# power_selectable_5v_3_3v.net
KiCad netlist of a schematic drawn in EAGLE
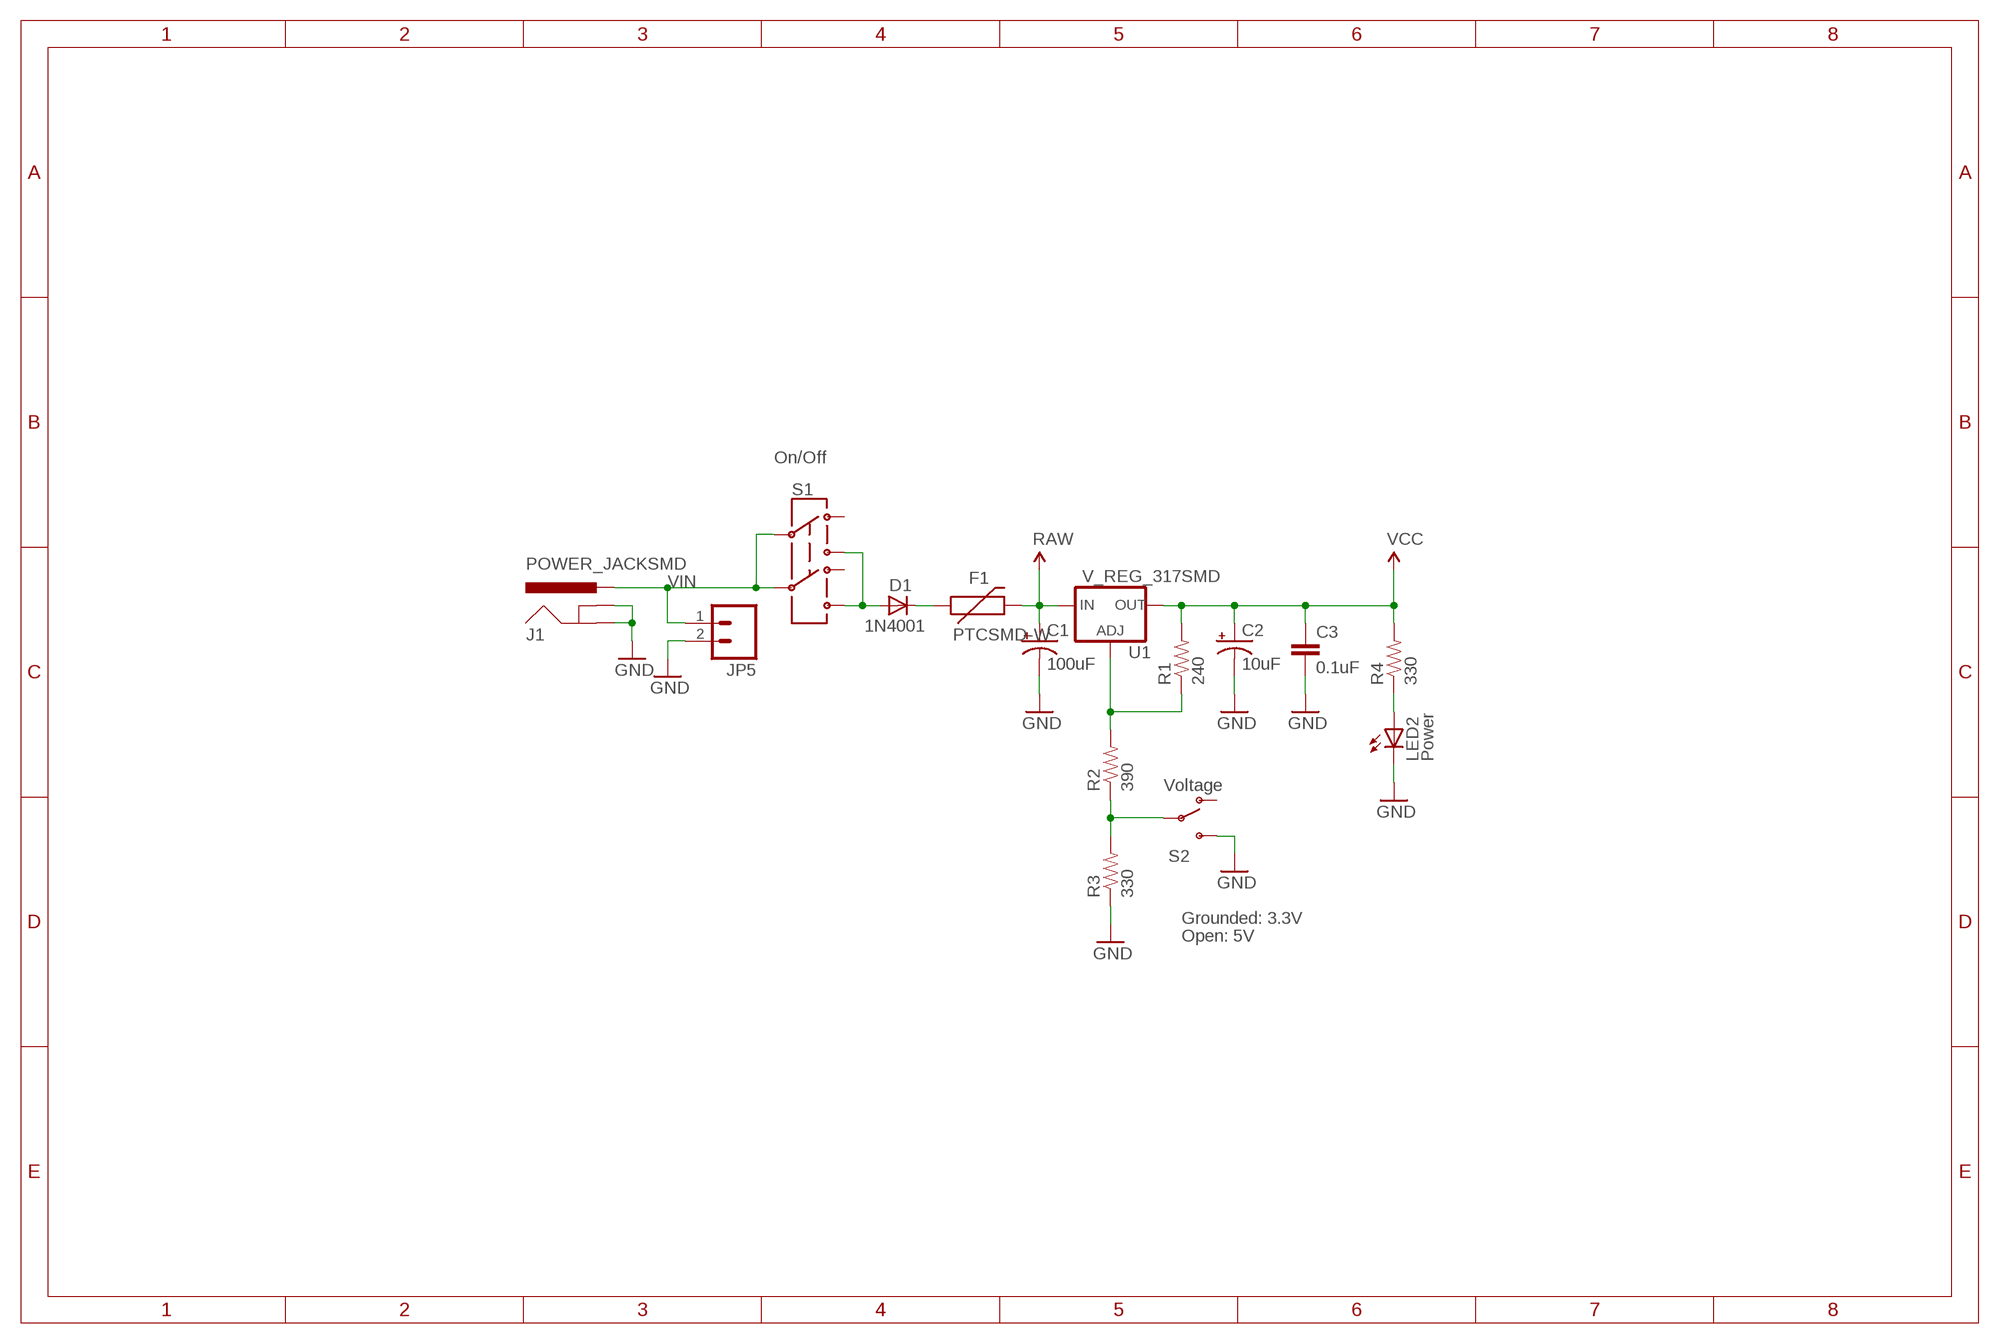
[diagram p0: schematic, sheet 1]

(export (version "E")
  (design (tool "Eeschema 10.0.6"))
  (components
    (comp (ref "C1")
      (value "100uF")
      (footprint "eagle-import:EIA7343")
      (libsource (lib "eagle-import") (part "CAP_POL7343"))
    )
    (comp (ref "C2")
      (value "10uF")
      (footprint "eagle-import:EIA3216")
      (libsource (lib "eagle-import") (part "CAP_POL1206"))
    )
    (comp (ref "C3")
      (value "0.1uF")
      (footprint "eagle-import:0603-CAP")
      (libsource (lib "eagle-import") (part "CAP0603-CAP"))
    )
    (comp (ref "D1")
      (value "1N4001")
      (footprint "eagle-import:SMA-DIODE-TYLERALT1")
      (libsource (lib "eagle-import") (part "DIODESMA-TYLERALT1"))
    )
    (comp (ref "F1")
      (value "PTCSMD-W")
      (footprint "eagle-import:PTC-1206-WIDE")
      (libsource (lib "eagle-import") (part "PTCSMD-W"))
    )
    (comp (ref "J1")
      (value "POWER_JACKSMD")
      (footprint "eagle-import:POWER_JACK_SMD")
      (libsource (lib "eagle-import") (part "POWER_JACKSMD"))
    )
    (comp (ref "JP5")
      (value "M02PTH")
      (footprint "eagle-import:1X02")
      (libsource (lib "eagle-import") (part "M02PTH"))
    )
    (comp (ref "LED2")
      (value "Power")
      (footprint "eagle-import:LED-1206")
      (libsource (lib "eagle-import") (part "LED1206"))
    )
    (comp (ref "R1")
      (value "240")
      (footprint "eagle-import:0603-RES")
      (libsource (lib "eagle-import") (part "RESISTOR0603-RES"))
    )
    (comp (ref "R2")
      (value "390")
      (footprint "eagle-import:0603-RES")
      (libsource (lib "eagle-import") (part "RESISTOR0603-RES"))
    )
    (comp (ref "R3")
      (value "330")
      (footprint "eagle-import:0603-RES")
      (libsource (lib "eagle-import") (part "RESISTOR0603-RES"))
    )
    (comp (ref "R4")
      (value "330")
      (footprint "eagle-import:0603-RES")
      (libsource (lib "eagle-import") (part "RESISTOR0603-RES"))
    )
    (comp (ref "S1")
      (value "On/Off")
      (footprint "eagle-import:AYZ0202")
      (libsource (lib "eagle-import") (part "AYZ0202"))
    )
    (comp (ref "S2")
      (value "Voltage")
      (footprint "eagle-import:AYZ0202")
      (libsource (lib "eagle-import") (part "SWITCH-SPSTSMD"))
    )
    (comp (ref "U1")
      (value "V_REG_317SMD")
      (footprint "eagle-import:SOT223")
      (libsource (lib "eagle-import") (part "V_REG_317SMD"))
    )
  )
  (nets
    (net (code "1") (name "/VIN") (class "Default")
      (node (ref "J1") (pin "VIN0") (pinfunction "PWR_VIN0") (pintype "bidirectional"))
      (node (ref "JP5") (pin "1") (pinfunction "1_1") (pintype "passive"))
      (node (ref "S1") (pin "2") (pinfunction "2_2") (pintype "bidirectional"))
      (node (ref "S1") (pin "5") (pinfunction "5_5") (pintype "bidirectional"))
    )
    (net (code "2") (name "GND") (class "Default")
      (node (ref "C1") (pin "C") (pinfunction "-_C") (pintype "passive"))
      (node (ref "C2") (pin "C") (pinfunction "-_C") (pintype "passive"))
      (node (ref "C3") (pin "2") (pinfunction "2_2") (pintype "passive"))
      (node (ref "J1") (pin "GND") (pinfunction "GNDBREAK_GND") (pintype "bidirectional"))
      (node (ref "J1") (pin "P$4") (pinfunction "GND_P$4") (pintype "bidirectional"))
      (node (ref "JP5") (pin "2") (pinfunction "2_2") (pintype "passive"))
      (node (ref "LED2") (pin "C") (pinfunction "C_C") (pintype "passive"))
      (node (ref "R3") (pin "1") (pinfunction "1_1") (pintype "passive"))
      (node (ref "S2") (pin "3") (pinfunction "S_3") (pintype "passive"))
    )
    (net (code "3") (name "Net-(D1-PadC)") (class "Default")
      (node (ref "D1") (pin "C") (pinfunction "C_C") (pintype "passive"))
      (node (ref "F1") (pin "1") (pinfunction "1_1") (pintype "bidirectional"))
    )
    (net (code "4") (name "Net-(LED2-PadA)") (class "Default")
      (node (ref "LED2") (pin "A") (pinfunction "A_A") (pintype "passive"))
      (node (ref "R4") (pin "1") (pinfunction "1_1") (pintype "passive"))
    )
    (net (code "5") (name "Net-(S1-3)") (class "Default")
      (node (ref "D1") (pin "A") (pinfunction "A_A") (pintype "passive"))
      (node (ref "S1") (pin "1") (pinfunction "3_1") (pintype "bidirectional"))
      (node (ref "S1") (pin "4") (pinfunction "6_4") (pintype "bidirectional"))
    )
    (net (code "6") (name "Net-(S2-P)") (class "Default")
      (node (ref "R2") (pin "1") (pinfunction "1_1") (pintype "passive"))
      (node (ref "R3") (pin "2") (pinfunction "2_2") (pintype "passive"))
      (node (ref "S2") (pin "2") (pinfunction "P_2") (pintype "passive"))
    )
    (net (code "7") (name "Net-(U1-ADJ)") (class "Default")
      (node (ref "R1") (pin "1") (pinfunction "1_1") (pintype "passive"))
      (node (ref "R2") (pin "2") (pinfunction "2_2") (pintype "passive"))
      (node (ref "U1") (pin "1") (pinfunction "ADJ_1") (pintype "input"))
    )
    (net (code "8") (name "RAW") (class "Default")
      (node (ref "C1") (pin "A") (pinfunction "+_A") (pintype "passive"))
      (node (ref "F1") (pin "2") (pinfunction "2_2") (pintype "bidirectional"))
      (node (ref "U1") (pin "3") (pinfunction "IN_3") (pintype "input"))
    )
    (net (code "9") (name "VCC") (class "Default")
      (node (ref "C2") (pin "A") (pinfunction "+_A") (pintype "passive"))
      (node (ref "C3") (pin "1") (pinfunction "1_1") (pintype "passive"))
      (node (ref "R1") (pin "2") (pinfunction "2_2") (pintype "passive"))
      (node (ref "R4") (pin "2") (pinfunction "2_2") (pintype "passive"))
      (node (ref "U1") (pin "2") (pinfunction "OUT_2") (pintype "output"))
    )
    (net (code "10") (name "unconnected-(S1-1-Pad3)") (class "Default")
      (node (ref "S1") (pin "3") (pinfunction "1_3") (pintype "bidirectional"))
    )
    (net (code "11") (name "unconnected-(S1-4-Pad6)") (class "Default")
      (node (ref "S1") (pin "6") (pinfunction "4_6") (pintype "bidirectional"))
    )
    (net (code "12") (name "unconnected-(S2-O-Pad1)") (class "Default")
      (node (ref "S2") (pin "1") (pinfunction "O_1") (pintype "passive"))
    )
  )
)
